# quasi_bb_nano_controller.net
KiCad netlist of a schematic drawn in EAGLE
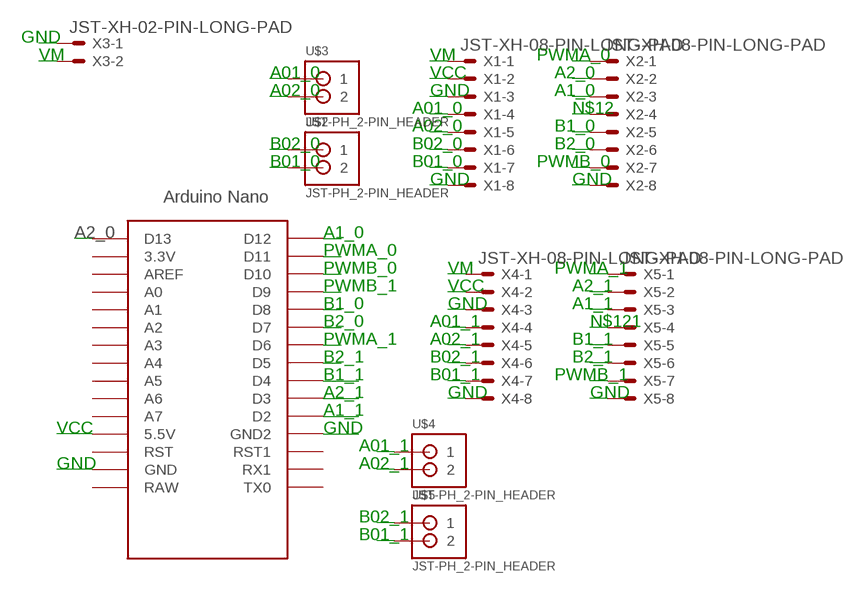
[diagram p0: schematic, sheet 1]

(export (version "E")
  (design (tool "Eeschema 10.0.6"))
  (components
    (comp (ref "U$1")
      (value "NANO")
      (footprint "eagle-import:NANO")
      (libsource (lib "eagle-import") (part "NANO"))
    )
    (comp (ref "U$2")
      (value "JST-PH_2-PIN_HEADER")
      (footprint "eagle-import:JST_B2B-PH_HEADER")
      (libsource (lib "eagle-import") (part "JST-PH_2-PIN_HEADER"))
    )
    (comp (ref "U$3")
      (value "JST-PH_2-PIN_HEADER")
      (footprint "eagle-import:JST_B2B-PH_HEADER")
      (libsource (lib "eagle-import") (part "JST-PH_2-PIN_HEADER"))
    )
    (comp (ref "U$4")
      (value "JST-PH_2-PIN_HEADER")
      (footprint "eagle-import:JST_B2B-PH_HEADER")
      (libsource (lib "eagle-import") (part "JST-PH_2-PIN_HEADER"))
    )
    (comp (ref "U$5")
      (value "JST-PH_2-PIN_HEADER")
      (footprint "eagle-import:JST_B2B-PH_HEADER")
      (libsource (lib "eagle-import") (part "JST-PH_2-PIN_HEADER"))
    )
    (comp (ref "X1")
      (value "JST-XH-08-PIN-LONG-PAD")
      (footprint "eagle-import:JST-XH-08-PACKAGE-LONG-PAD")
      (libsource (lib "eagle-import") (part "JST-XH-08-PIN-LONG-PAD"))
    )
    (comp (ref "X2")
      (value "JST-XH-08-PIN-LONG-PAD")
      (footprint "eagle-import:JST-XH-08-PACKAGE-LONG-PAD")
      (libsource (lib "eagle-import") (part "JST-XH-08-PIN-LONG-PAD"))
    )
    (comp (ref "X3")
      (value "JST-XH-02-PIN-LONG-PAD")
      (footprint "eagle-import:JST-XH-02-PACKAGE-LONG-PAD")
      (libsource (lib "eagle-import") (part "JST-XH-02-PIN-LONG-PAD"))
    )
    (comp (ref "X4")
      (value "JST-XH-08-PIN-LONG-PAD")
      (footprint "eagle-import:JST-XH-08-PACKAGE-LONG-PAD")
      (libsource (lib "eagle-import") (part "JST-XH-08-PIN-LONG-PAD"))
    )
    (comp (ref "X5")
      (value "JST-XH-08-PIN-LONG-PAD")
      (footprint "eagle-import:JST-XH-08-PACKAGE-LONG-PAD")
      (libsource (lib "eagle-import") (part "JST-XH-08-PIN-LONG-PAD"))
    )
  )
  (nets
    (net (code "1") (name "/A01_0") (class "Default")
      (node (ref "U$3") (pin "P1") (pinfunction "1_P1") (pintype "bidirectional"))
      (node (ref "X1") (pin "4") (pinfunction "S_4") (pintype "passive"))
    )
    (net (code "2") (name "/A1_0") (class "Default")
      (node (ref "U$1") (pin "D12") (pinfunction "D12_D12") (pintype "bidirectional"))
      (node (ref "X2") (pin "3") (pinfunction "S_3") (pintype "passive"))
    )
    (net (code "3") (name "/A01_1") (class "Default")
      (node (ref "U$4") (pin "P1") (pinfunction "1_P1") (pintype "bidirectional"))
      (node (ref "X4") (pin "4") (pinfunction "S_4") (pintype "passive"))
    )
    (net (code "4") (name "/A1_1") (class "Default")
      (node (ref "U$1") (pin "D2") (pinfunction "D2_D2") (pintype "bidirectional"))
      (node (ref "X5") (pin "3") (pinfunction "S_3") (pintype "passive"))
    )
    (net (code "5") (name "/A02_0") (class "Default")
      (node (ref "U$3") (pin "P2") (pinfunction "2_P2") (pintype "bidirectional"))
      (node (ref "X1") (pin "5") (pinfunction "S_5") (pintype "passive"))
    )
    (net (code "6") (name "/A2_0") (class "Default")
      (node (ref "U$1") (pin "D13") (pinfunction "D13_D13") (pintype "bidirectional"))
      (node (ref "X2") (pin "2") (pinfunction "S_2") (pintype "passive"))
    )
    (net (code "7") (name "/A2_1") (class "Default")
      (node (ref "U$1") (pin "D3") (pinfunction "D3_D3") (pintype "bidirectional"))
      (node (ref "X5") (pin "2") (pinfunction "S_2") (pintype "passive"))
    )
    (net (code "8") (name "/A02_1") (class "Default")
      (node (ref "U$4") (pin "P2") (pinfunction "2_P2") (pintype "bidirectional"))
      (node (ref "X4") (pin "5") (pinfunction "S_5") (pintype "passive"))
    )
    (net (code "9") (name "/B01_0") (class "Default")
      (node (ref "U$2") (pin "P2") (pinfunction "2_P2") (pintype "bidirectional"))
      (node (ref "X1") (pin "7") (pinfunction "S_7") (pintype "passive"))
    )
    (net (code "10") (name "/B1_0") (class "Default")
      (node (ref "U$1") (pin "D8") (pinfunction "D8_D8") (pintype "bidirectional"))
      (node (ref "X2") (pin "5") (pinfunction "S_5") (pintype "passive"))
    )
    (net (code "11") (name "/B1_1") (class "Default")
      (node (ref "U$1") (pin "D4") (pinfunction "D4_D4") (pintype "bidirectional"))
      (node (ref "X5") (pin "5") (pinfunction "S_5") (pintype "passive"))
    )
    (net (code "12") (name "/B01_1") (class "Default")
      (node (ref "U$5") (pin "P2") (pinfunction "2_P2") (pintype "bidirectional"))
      (node (ref "X4") (pin "7") (pinfunction "S_7") (pintype "passive"))
    )
    (net (code "13") (name "/B2_0") (class "Default")
      (node (ref "U$1") (pin "D7") (pinfunction "D7_D7") (pintype "bidirectional"))
      (node (ref "X2") (pin "6") (pinfunction "S_6") (pintype "passive"))
    )
    (net (code "14") (name "/B02_0") (class "Default")
      (node (ref "U$2") (pin "P1") (pinfunction "1_P1") (pintype "bidirectional"))
      (node (ref "X1") (pin "6") (pinfunction "S_6") (pintype "passive"))
    )
    (net (code "15") (name "/B2_1") (class "Default")
      (node (ref "U$1") (pin "D5") (pinfunction "D5_D5") (pintype "bidirectional"))
      (node (ref "X5") (pin "6") (pinfunction "S_6") (pintype "passive"))
    )
    (net (code "16") (name "/B02_1") (class "Default")
      (node (ref "U$5") (pin "P1") (pinfunction "1_P1") (pintype "bidirectional"))
      (node (ref "X4") (pin "6") (pinfunction "S_6") (pintype "passive"))
    )
    (net (code "17") (name "/GND") (class "Default")
      (node (ref "U$1") (pin "GND") (pinfunction "GND_GND") (pintype "bidirectional"))
      (node (ref "U$1") (pin "GND1") (pinfunction "GND2_GND1") (pintype "bidirectional"))
      (node (ref "X1") (pin "3") (pinfunction "S_3") (pintype "passive"))
      (node (ref "X1") (pin "8") (pinfunction "S_8") (pintype "passive"))
      (node (ref "X2") (pin "8") (pinfunction "S_8") (pintype "passive"))
      (node (ref "X3") (pin "1") (pinfunction "S_1") (pintype "passive"))
      (node (ref "X4") (pin "3") (pinfunction "S_3") (pintype "passive"))
      (node (ref "X4") (pin "8") (pinfunction "S_8") (pintype "passive"))
      (node (ref "X5") (pin "8") (pinfunction "S_8") (pintype "passive"))
    )
    (net (code "18") (name "/N$12") (class "Default")
      (node (ref "X2") (pin "4") (pinfunction "S_4") (pintype "passive"))
    )
    (net (code "19") (name "/N$121") (class "Default")
      (node (ref "X5") (pin "4") (pinfunction "S_4") (pintype "passive"))
    )
    (net (code "20") (name "/PWMA_0") (class "Default")
      (node (ref "U$1") (pin "D11") (pinfunction "D11_D11") (pintype "bidirectional"))
      (node (ref "X2") (pin "1") (pinfunction "S_1") (pintype "passive"))
    )
    (net (code "21") (name "/PWMA_1") (class "Default")
      (node (ref "U$1") (pin "D6") (pinfunction "D6_D6") (pintype "bidirectional"))
      (node (ref "X5") (pin "1") (pinfunction "S_1") (pintype "passive"))
    )
    (net (code "22") (name "/PWMB_0") (class "Default")
      (node (ref "U$1") (pin "D10") (pinfunction "D10_D10") (pintype "bidirectional"))
      (node (ref "X2") (pin "7") (pinfunction "S_7") (pintype "passive"))
    )
    (net (code "23") (name "/PWMB_1") (class "Default")
      (node (ref "U$1") (pin "D9") (pinfunction "D9_D9") (pintype "bidirectional"))
      (node (ref "X5") (pin "7") (pinfunction "S_7") (pintype "passive"))
    )
    (net (code "24") (name "/VCC") (class "Default")
      (node (ref "U$1") (pin "5V") (pinfunction "5.5V_5V") (pintype "bidirectional"))
      (node (ref "X1") (pin "2") (pinfunction "S_2") (pintype "passive"))
      (node (ref "X4") (pin "2") (pinfunction "S_2") (pintype "passive"))
    )
    (net (code "25") (name "/VM") (class "Default")
      (node (ref "X1") (pin "1") (pinfunction "S_1") (pintype "passive"))
      (node (ref "X3") (pin "2") (pinfunction "S_2") (pintype "passive"))
      (node (ref "X4") (pin "1") (pinfunction "S_1") (pintype "passive"))
    )
    (net (code "26") (name "unconnected-(U$1-Pad3.3V)") (class "Default")
      (node (ref "U$1") (pin "3.3V") (pinfunction "3.3V_3.3V") (pintype "bidirectional"))
    )
    (net (code "27") (name "unconnected-(U$1-PadA0)") (class "Default")
      (node (ref "U$1") (pin "A0") (pinfunction "A0_A0") (pintype "bidirectional"))
    )
    (net (code "28") (name "unconnected-(U$1-PadA1)") (class "Default")
      (node (ref "U$1") (pin "A1") (pinfunction "A1_A1") (pintype "bidirectional"))
    )
    (net (code "29") (name "unconnected-(U$1-PadA2)") (class "Default")
      (node (ref "U$1") (pin "A2") (pinfunction "A2_A2") (pintype "bidirectional"))
    )
    (net (code "30") (name "unconnected-(U$1-PadA3)") (class "Default")
      (node (ref "U$1") (pin "A3") (pinfunction "A3_A3") (pintype "bidirectional"))
    )
    (net (code "31") (name "unconnected-(U$1-PadA4)") (class "Default")
      (node (ref "U$1") (pin "A4") (pinfunction "A4_A4") (pintype "bidirectional"))
    )
    (net (code "32") (name "unconnected-(U$1-PadA5)") (class "Default")
      (node (ref "U$1") (pin "A5") (pinfunction "A5_A5") (pintype "bidirectional"))
    )
    (net (code "33") (name "unconnected-(U$1-PadA6)") (class "Default")
      (node (ref "U$1") (pin "A6") (pinfunction "A6_A6") (pintype "bidirectional"))
    )
    (net (code "34") (name "unconnected-(U$1-PadA7)") (class "Default")
      (node (ref "U$1") (pin "A7") (pinfunction "A7_A7") (pintype "bidirectional"))
    )
    (net (code "35") (name "unconnected-(U$1-PadAREF)") (class "Default")
      (node (ref "U$1") (pin "AREF") (pinfunction "AREF_AREF") (pintype "bidirectional"))
    )
    (net (code "36") (name "unconnected-(U$1-PadICSP1)") (class "Default")
      (node (ref "U$1") (pin "ICSP1") (pinfunction "ICSP1_ICSP1") (pintype "bidirectional"))
    )
    (net (code "37") (name "unconnected-(U$1-PadICSP2)") (class "Default")
      (node (ref "U$1") (pin "ICSP2") (pinfunction "ICSP2_ICSP2") (pintype "bidirectional"))
    )
    (net (code "38") (name "unconnected-(U$1-PadICSP3)") (class "Default")
      (node (ref "U$1") (pin "ICSP3") (pinfunction "ICSP3_ICSP3") (pintype "bidirectional"))
    )
    (net (code "39") (name "unconnected-(U$1-PadICSP4)") (class "Default")
      (node (ref "U$1") (pin "ICSP4") (pinfunction "ICSP4_ICSP4") (pintype "bidirectional"))
    )
    (net (code "40") (name "unconnected-(U$1-PadICSP5)") (class "Default")
      (node (ref "U$1") (pin "ICSP5") (pinfunction "ICSP5_ICSP5") (pintype "bidirectional"))
    )
    (net (code "41") (name "unconnected-(U$1-PadICSP6)") (class "Default")
      (node (ref "U$1") (pin "ICSP6") (pinfunction "ICSP6_ICSP6") (pintype "bidirectional"))
    )
    (net (code "42") (name "unconnected-(U$1-PadRAW)") (class "Default")
      (node (ref "U$1") (pin "RAW") (pinfunction "RAW_RAW") (pintype "bidirectional"))
    )
    (net (code "43") (name "unconnected-(U$1-PadRST)") (class "Default")
      (node (ref "U$1") (pin "RST") (pinfunction "RST_RST") (pintype "bidirectional"))
    )
    (net (code "44") (name "unconnected-(U$1-PadRST1)") (class "Default")
      (node (ref "U$1") (pin "RST1") (pinfunction "RST1_RST1") (pintype "bidirectional"))
    )
    (net (code "45") (name "unconnected-(U$1-PadRX1)") (class "Default")
      (node (ref "U$1") (pin "RX1") (pinfunction "RX1_RX1") (pintype "bidirectional"))
    )
    (net (code "46") (name "unconnected-(U$1-PadTX0)") (class "Default")
      (node (ref "U$1") (pin "TX0") (pinfunction "TX0_TX0") (pintype "bidirectional"))
    )
  )
)
